# Buffers.net
KiCad netlist of a schematic drawn in Altium Designer
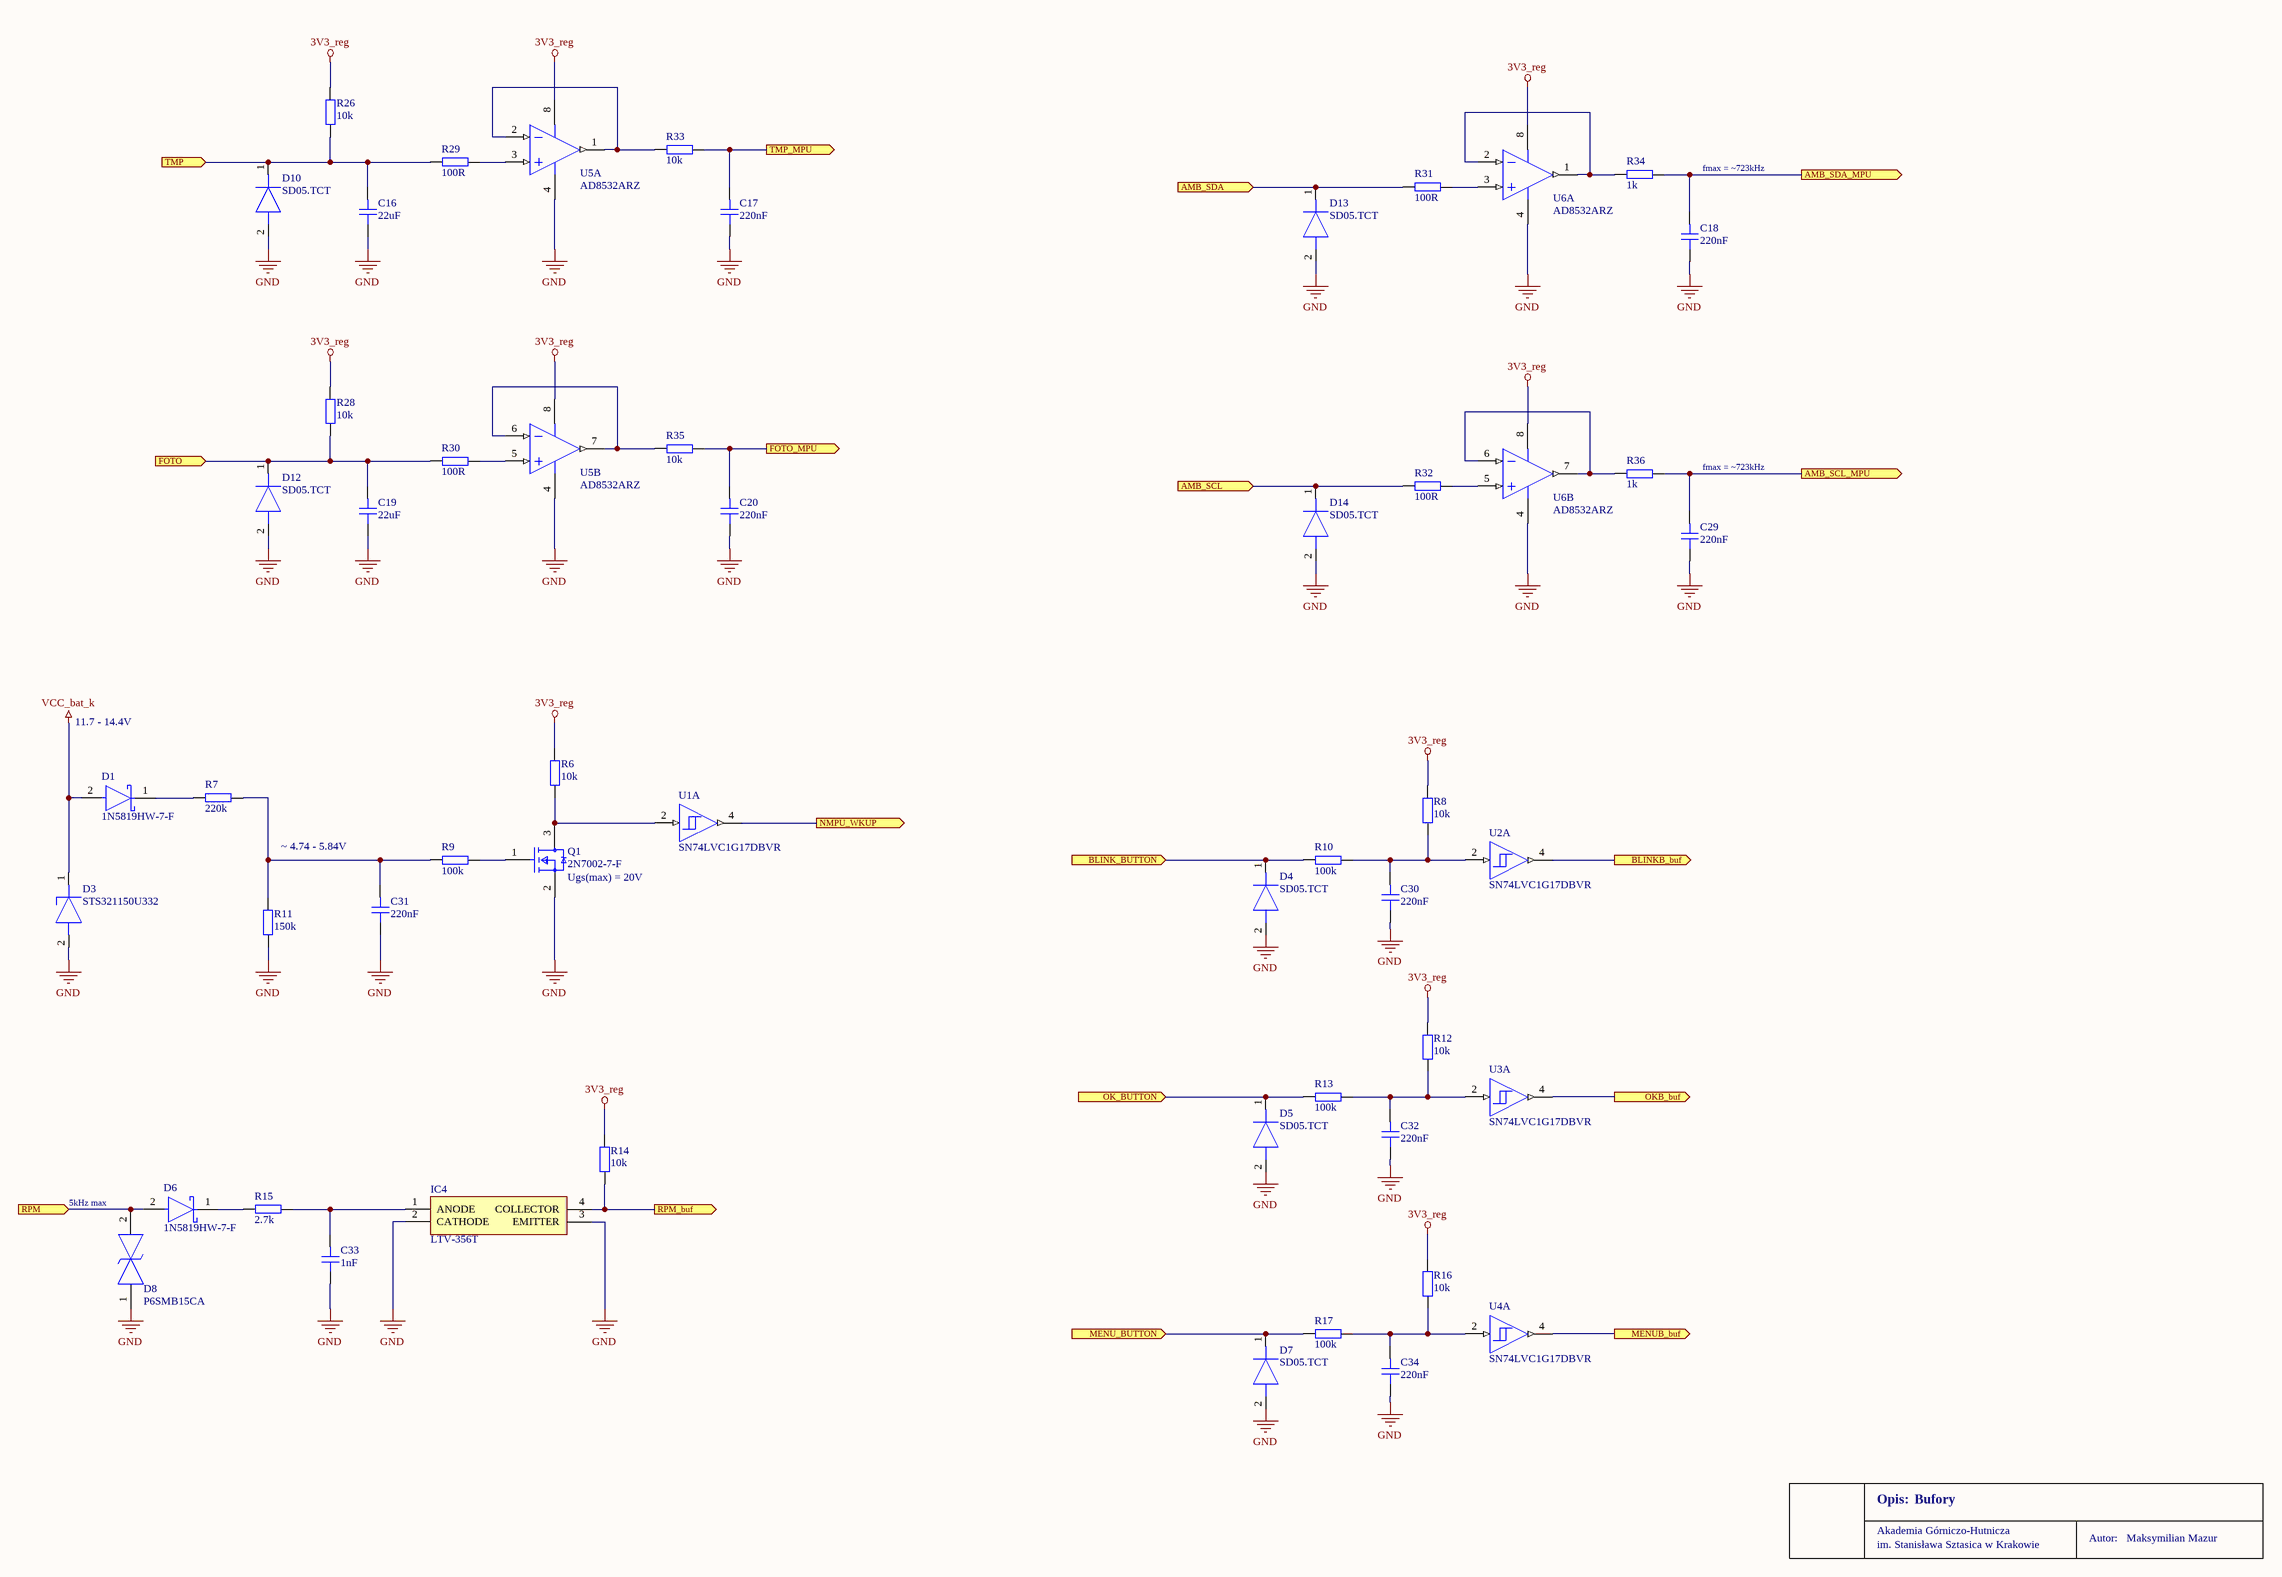
[diagram p0: Buffers.SchDoc]

(export (version "E")
  (design (tool "Eeschema 10.0.6"))
  (components
    (comp (ref "C16")
      (value "22uF")
      (footprint "CAP_0603")
      (description "Capacitor SMD 0603\r\nX7R\r\nLOW ESR")
      (libsource (lib "Schematic-Lib-PhilsLab") (part "CAP_0603"))
    )
    (comp (ref "C17")
      (value "220nF")
      (footprint "CAP_0603")
      (description "Capacitor SMD 0603\r\nX7R\r\nLOW ESR")
      (libsource (lib "Schematic-Lib-PhilsLab") (part "CAP_0603"))
    )
    (comp (ref "C18")
      (value "220nF")
      (footprint "CAP_0603")
      (description "Capacitor SMD 0603\r\nX7R\r\nLOW ESR")
      (libsource (lib "Schematic-Lib-PhilsLab") (part "CAP_0603"))
    )
    (comp (ref "C19")
      (value "22uF")
      (footprint "CAP_0603")
      (description "Capacitor SMD 0603\r\nX7R\r\nLOW ESR")
      (libsource (lib "Schematic-Lib-PhilsLab") (part "CAP_0603"))
    )
    (comp (ref "C20")
      (value "220nF")
      (footprint "CAP_0603")
      (description "Capacitor SMD 0603\r\nX7R\r\nLOW ESR")
      (libsource (lib "Schematic-Lib-PhilsLab") (part "CAP_0603"))
    )
    (comp (ref "C29")
      (value "220nF")
      (footprint "CAP_0603")
      (description "Capacitor SMD 0603\r\nX7R\r\nLOW ESR")
      (libsource (lib "Schematic-Lib-PhilsLab") (part "CAP_0603"))
    )
    (comp (ref "C30")
      (value "220nF")
      (footprint "CAP_0603")
      (description "Capacitor SMD 0603\r\nX7R\r\nLOW ESR")
      (libsource (lib "Schematic-Lib-PhilsLab") (part "CAP_0603"))
    )
    (comp (ref "C31")
      (value "220nF")
      (footprint "CAP_0603")
      (description "Capacitor SMD 0603\r\nX7R\r\nLOW ESR")
      (libsource (lib "Schematic-Lib-PhilsLab") (part "CAP_0603"))
    )
    (comp (ref "C32")
      (value "220nF")
      (footprint "CAP_0603")
      (description "Capacitor SMD 0603\r\nX7R\r\nLOW ESR")
      (libsource (lib "Schematic-Lib-PhilsLab") (part "CAP_0603"))
    )
    (comp (ref "C33")
      (value "1nF")
      (footprint "CAP_0603")
      (description "Capacitor SMD 0603\r\nX7R\r\nLOW ESR")
      (libsource (lib "Schematic-Lib-PhilsLab") (part "CAP_0603"))
    )
    (comp (ref "C34")
      (value "220nF")
      (footprint "CAP_0603")
      (description "Capacitor SMD 0603\r\nX7R\r\nLOW ESR")
      (libsource (lib "Schematic-Lib-PhilsLab") (part "CAP_0603"))
    )
    (comp (ref "D1")
      (value "1N5819HW-7-F")
      (footprint "FP-SOD123-IPC_A")
      (description "DIODE SCHOTTKY 40V 1A SOD123")
      (libsource (lib "Altium Content Vault") (part "1d6ec82d83fb6aee721767c19dac4b9"))
    )
    (comp (ref "D3")
      (value "STS321150U332")
      (footprint "SamacSys:SOD2613X100N")
      (description "Diode ESD (Uni-directional)\r\n\r\nSOD-323 \r\n16V 330pF")
      (fields (field (name "MANUFACTURER_PART_NUMBER") "STS321150U751"))
      (libsource (lib "*") (part "STS321150U751"))
    )
    (comp (ref "D4")
      (value "SD05.TCT")
      (footprint "SamacSys:SOD2513X110N")
      (description "Diode")
      (fields (field (name "MOUSER PART NUMBER") "947-SD05.TCT"))
      (libsource (lib "*") (part "SD05.TCT"))
    )
    (comp (ref "D5")
      (value "SD05.TCT")
      (footprint "SamacSys:SOD2513X110N")
      (description "Diode")
      (fields (field (name "MOUSER PART NUMBER") "947-SD05.TCT"))
      (libsource (lib "*") (part "SD05.TCT"))
    )
    (comp (ref "D6")
      (value "1N5819HW-7-F")
      (footprint "FP-SOD123-IPC_A")
      (description "DIODE SCHOTTKY 40V 1A SOD123")
      (libsource (lib "Altium Content Vault") (part "1d6ec82d83fb6aee721767c19dac4b9"))
    )
    (comp (ref "D7")
      (value "SD05.TCT")
      (footprint "SamacSys:SOD2513X110N")
      (description "Diode")
      (fields (field (name "MOUSER PART NUMBER") "947-SD05.TCT"))
      (libsource (lib "*") (part "SD05.TCT"))
    )
    (comp (ref "D8")
      (value "P6SMB15CA")
      (footprint "SamacSys:DIONM5436X261N")
      (description "TVS Diode (Bi-directional)")
      (fields (field (name "MOUSER PART NUMBER") "576-P6SMB15CA"))
      (libsource (lib "*") (part "P6SMB15CA"))
    )
    (comp (ref "D10")
      (value "SD05.TCT")
      (footprint "SamacSys:SOD2513X110N")
      (description "Diode")
      (fields (field (name "MOUSER PART NUMBER") "947-SD05.TCT"))
      (libsource (lib "*") (part "SD05.TCT"))
    )
    (comp (ref "D12")
      (value "SD05.TCT")
      (footprint "SamacSys:SOD2513X110N")
      (description "Diode")
      (fields (field (name "MOUSER PART NUMBER") "947-SD05.TCT"))
      (libsource (lib "*") (part "SD05.TCT"))
    )
    (comp (ref "D13")
      (value "SD05.TCT")
      (footprint "SamacSys:SOD2513X110N")
      (description "Diode")
      (fields (field (name "MOUSER PART NUMBER") "947-SD05.TCT"))
      (libsource (lib "*") (part "SD05.TCT"))
    )
    (comp (ref "D14")
      (value "SD05.TCT")
      (footprint "SamacSys:SOD2513X110N")
      (description "Diode")
      (fields (field (name "MOUSER PART NUMBER") "947-SD05.TCT"))
      (libsource (lib "*") (part "SD05.TCT"))
    )
    (comp (ref "IC4")
      (value "LTV-356T")
      (footprint "SamacSys:SOP254P675X220-4N")
      (description "Integrated Circuit")
      (fields (field (name "MOUSER PART NUMBER") "859-LTV-356T"))
      (libsource (lib "*") (part "LTV-356T"))
    )
    (comp (ref "Q1")
      (value "2N7002-7-F")
      (footprint "FP-SOT23-MFG")
      (description "MOSFET N-CH 60V 115MA SOT23-3")
      (fields (field (name "VOLTAGE") "60V"))
      (libsource (lib "Altium Content Vault") (part "3b9c635fedb024a5347a57b145af9cc"))
    )
    (comp (ref "R6")
      (value "10k")
      (footprint "RES_0603")
      (description "Resistor SMD 0603")
      (libsource (lib "Schematic-Lib-PhilsLab") (part "RES_0603"))
    )
    (comp (ref "R7")
      (value "220k")
      (footprint "RES_0603")
      (description "Resistor SMD 0603")
      (libsource (lib "Schematic-Lib-PhilsLab") (part "RES_0603"))
    )
    (comp (ref "R8")
      (value "10k")
      (footprint "RES_0603")
      (description "Resistor SMD 0603")
      (libsource (lib "Schematic-Lib-PhilsLab") (part "RES_0603"))
    )
    (comp (ref "R9")
      (value "100k")
      (footprint "RES_0603")
      (description "Resistor SMD 0603")
      (libsource (lib "Schematic-Lib-PhilsLab") (part "RES_0603"))
    )
    (comp (ref "R10")
      (value "100k")
      (footprint "RES_0603")
      (description "Resistor SMD 0603")
      (libsource (lib "Schematic-Lib-PhilsLab") (part "RES_0603"))
    )
    (comp (ref "R11")
      (value "150k")
      (footprint "RES_0603")
      (description "Resistor SMD 0603")
      (libsource (lib "Schematic-Lib-PhilsLab") (part "RES_0603"))
    )
    (comp (ref "R12")
      (value "10k")
      (footprint "RES_0603")
      (description "Resistor SMD 0603")
      (libsource (lib "Schematic-Lib-PhilsLab") (part "RES_0603"))
    )
    (comp (ref "R13")
      (value "100k")
      (footprint "RES_0603")
      (description "Resistor SMD 0603")
      (libsource (lib "Schematic-Lib-PhilsLab") (part "RES_0603"))
    )
    (comp (ref "R14")
      (value "10k")
      (footprint "RES_0603")
      (description "Resistor SMD 0603")
      (libsource (lib "Schematic-Lib-PhilsLab") (part "RES_0603"))
    )
    (comp (ref "R15")
      (value "2.7k")
      (footprint "RES_0603")
      (description "Resistor SMD 0603")
      (libsource (lib "Schematic-Lib-PhilsLab") (part "RES_0603"))
    )
    (comp (ref "R16")
      (value "10k")
      (footprint "RES_0603")
      (description "Resistor SMD 0603")
      (libsource (lib "Schematic-Lib-PhilsLab") (part "RES_0603"))
    )
    (comp (ref "R17")
      (value "100k")
      (footprint "RES_0603")
      (description "Resistor SMD 0603")
      (libsource (lib "Schematic-Lib-PhilsLab") (part "RES_0603"))
    )
    (comp (ref "R26")
      (value "10k")
      (footprint "RES_0603")
      (description "Resistor SMD 0603")
      (libsource (lib "Schematic-Lib-PhilsLab") (part "RES_0603"))
    )
    (comp (ref "R28")
      (value "10k")
      (footprint "RES_0603")
      (description "Resistor SMD 0603")
      (libsource (lib "Schematic-Lib-PhilsLab") (part "RES_0603"))
    )
    (comp (ref "R29")
      (value "100R")
      (footprint "RES_0603")
      (description "Resistor SMD 0603")
      (libsource (lib "Schematic-Lib-PhilsLab") (part "RES_0603"))
    )
    (comp (ref "R30")
      (value "100R")
      (footprint "RES_0603")
      (description "Resistor SMD 0603")
      (libsource (lib "Schematic-Lib-PhilsLab") (part "RES_0603"))
    )
    (comp (ref "R31")
      (value "100R")
      (footprint "RES_0603")
      (description "Resistor SMD 0603")
      (libsource (lib "Schematic-Lib-PhilsLab") (part "RES_0603"))
    )
    (comp (ref "R32")
      (value "100R")
      (footprint "RES_0603")
      (description "Resistor SMD 0603")
      (libsource (lib "Schematic-Lib-PhilsLab") (part "RES_0603"))
    )
    (comp (ref "R33")
      (value "10k")
      (footprint "RES_0603")
      (description "Resistor SMD 0603")
      (libsource (lib "Schematic-Lib-PhilsLab") (part "RES_0603"))
    )
    (comp (ref "R34")
      (value "1k")
      (footprint "RES_0603")
      (description "Resistor SMD 0603")
      (libsource (lib "Schematic-Lib-PhilsLab") (part "RES_0603"))
    )
    (comp (ref "R35")
      (value "10k")
      (footprint "RES_0603")
      (description "Resistor SMD 0603")
      (libsource (lib "Schematic-Lib-PhilsLab") (part "RES_0603"))
    )
    (comp (ref "R36")
      (value "1k")
      (footprint "RES_0603")
      (description "Resistor SMD 0603")
      (libsource (lib "Schematic-Lib-PhilsLab") (part "RES_0603"))
    )
    (comp (ref "U1")
      (value "SN74LVC1G17DBVR")
      (footprint "DBV0005A_L")
      (description "Single Schmitt-Trigger Buffer, DBV0005A, LARGE T&R")
      (fields
        (field (name "MANUFACTURER") "Texas Instruments")
        (field (name "GENERIC PART NUMBER") "SN74LVC1G17")
      )
      (libsource (lib "Altium Content Vault") (part "TI-SN74XXX1XXX-XX-5-SCHMITT"))
    )
    (comp (ref "U2")
      (value "SN74LVC1G17DBVR")
      (footprint "DBV0005A_L")
      (description "Single Schmitt-Trigger Buffer, DBV0005A, LARGE T&R")
      (fields
        (field (name "MANUFACTURER") "Texas Instruments")
        (field (name "GENERIC PART NUMBER") "SN74LVC1G17")
      )
      (libsource (lib "Altium Content Vault") (part "TI-SN74XXX1XXX-XX-5-SCHMITT"))
    )
    (comp (ref "U3")
      (value "SN74LVC1G17DBVR")
      (footprint "DBV0005A_L")
      (description "Single Schmitt-Trigger Buffer, DBV0005A, LARGE T&R")
      (fields
        (field (name "MANUFACTURER") "Texas Instruments")
        (field (name "GENERIC PART NUMBER") "SN74LVC1G17")
      )
      (libsource (lib "Altium Content Vault") (part "TI-SN74XXX1XXX-XX-5-SCHMITT"))
    )
    (comp (ref "U4")
      (value "SN74LVC1G17DBVR")
      (footprint "DBV0005A_L")
      (description "Single Schmitt-Trigger Buffer, DBV0005A, LARGE T&R")
      (fields
        (field (name "MANUFACTURER") "Texas Instruments")
        (field (name "GENERIC PART NUMBER") "SN74LVC1G17")
      )
      (libsource (lib "Altium Content Vault") (part "TI-SN74XXX1XXX-XX-5-SCHMITT"))
    )
    (comp (ref "U5")
      (value "AD8532ARZ")
      (footprint "ADI-R-8_L")
      (fields (field (name "GENERIC PART NUMBER") "AD8532") (field (name "MANUFACTURER") "Analog Devices"))
      (libsource (lib "Altium Content Vault") (part "ADI-OP29X-R-8"))
    )
    (comp (ref "U6")
      (value "AD8532ARZ")
      (footprint "ADI-R-8_L")
      (fields (field (name "GENERIC PART NUMBER") "AD8532") (field (name "MANUFACTURER") "Analog Devices"))
      (libsource (lib "Altium Content Vault") (part "ADI-OP29X-R-8"))
    )
  )
  (nets
    (net (code "1") (name "/AMB_SCL") (class "Default")
      (node (ref "D14") (pin "1") (pinfunction "K_1") (pintype "passive"))
      (node (ref "R32") (pin "2") (pinfunction "2_2") (pintype "passive"))
    )
    (net (code "2") (name "/AMB_SCL_MPU") (class "Default")
      (node (ref "C29") (pin "1") (pinfunction "1_1") (pintype "passive"))
      (node (ref "R36") (pin "1") (pinfunction "1_1") (pintype "passive"))
    )
    (net (code "3") (name "/AMB_SDA") (class "Default")
      (node (ref "D13") (pin "1") (pinfunction "K_1") (pintype "passive"))
      (node (ref "R31") (pin "2") (pinfunction "2_2") (pintype "passive"))
    )
    (net (code "4") (name "/AMB_SDA_MPU") (class "Default")
      (node (ref "C18") (pin "1") (pinfunction "1_1") (pintype "passive"))
      (node (ref "R34") (pin "1") (pinfunction "1_1") (pintype "passive"))
    )
    (net (code "5") (name "/BLINKB_buf") (class "Default")
      (node (ref "U2") (pin "4") (pinfunction "Y_4") (pintype "output"))
    )
    (net (code "6") (name "/BLINK_BUTTON") (class "Default")
      (node (ref "D4") (pin "1") (pinfunction "K_1") (pintype "passive"))
      (node (ref "R10") (pin "2") (pinfunction "2_2") (pintype "passive"))
    )
    (net (code "7") (name "/FOTO") (class "Default")
      (node (ref "C19") (pin "1") (pinfunction "1_1") (pintype "passive"))
      (node (ref "D12") (pin "1") (pinfunction "K_1") (pintype "passive"))
      (node (ref "R28") (pin "1") (pinfunction "1_1") (pintype "passive"))
      (node (ref "R30") (pin "2") (pinfunction "2_2") (pintype "passive"))
    )
    (net (code "8") (name "/FOTO_MPU") (class "Default")
      (node (ref "C20") (pin "1") (pinfunction "1_1") (pintype "passive"))
      (node (ref "R35") (pin "1") (pinfunction "1_1") (pintype "passive"))
    )
    (net (code "9") (name "/MENUB_buf") (class "Default")
      (node (ref "U4") (pin "4") (pinfunction "Y_4") (pintype "output"))
    )
    (net (code "10") (name "/MENU_BUTTON") (class "Default")
      (node (ref "D7") (pin "1") (pinfunction "K_1") (pintype "passive"))
      (node (ref "R17") (pin "2") (pinfunction "2_2") (pintype "passive"))
    )
    (net (code "11") (name "/NMPU_WKUP") (class "Default")
      (node (ref "U1") (pin "4") (pinfunction "Y_4") (pintype "output"))
    )
    (net (code "12") (name "/OKB_buf") (class "Default")
      (node (ref "U3") (pin "4") (pinfunction "Y_4") (pintype "output"))
    )
    (net (code "13") (name "/OK_BUTTON") (class "Default")
      (node (ref "D5") (pin "1") (pinfunction "K_1") (pintype "passive"))
      (node (ref "R13") (pin "2") (pinfunction "2_2") (pintype "passive"))
    )
    (net (code "14") (name "/RPM") (class "Default")
      (node (ref "D6") (pin "2") (pinfunction "A_2") (pintype "passive"))
      (node (ref "D8") (pin "2") (pinfunction "2_2") (pintype "passive"))
    )
    (net (code "15") (name "/RPM_buf") (class "Default")
      (node (ref "IC4") (pin "4") (pinfunction "COLLECTOR_4") (pintype "passive"))
      (node (ref "R14") (pin "2") (pinfunction "2_2") (pintype "passive"))
    )
    (net (code "16") (name "/TMP") (class "Default")
      (node (ref "C16") (pin "1") (pinfunction "1_1") (pintype "passive"))
      (node (ref "D10") (pin "1") (pinfunction "K_1") (pintype "passive"))
      (node (ref "R26") (pin "1") (pinfunction "1_1") (pintype "passive"))
      (node (ref "R29") (pin "2") (pinfunction "2_2") (pintype "passive"))
    )
    (net (code "17") (name "/TMP_MPU") (class "Default")
      (node (ref "C17") (pin "1") (pinfunction "1_1") (pintype "passive"))
      (node (ref "R33") (pin "1") (pinfunction "1_1") (pintype "passive"))
    )
    (net (code "18") (name "3V3_reg") (class "Default")
      (node (ref "R12") (pin "1") (pinfunction "1_1") (pintype "passive"))
      (node (ref "R14") (pin "1") (pinfunction "1_1") (pintype "passive"))
      (node (ref "R16") (pin "1") (pinfunction "1_1") (pintype "passive"))
      (node (ref "R26") (pin "2") (pinfunction "2_2") (pintype "passive"))
      (node (ref "R28") (pin "2") (pinfunction "2_2") (pintype "passive"))
      (node (ref "R6") (pin "1") (pinfunction "1_1") (pintype "passive"))
      (node (ref "R8") (pin "1") (pinfunction "1_1") (pintype "passive"))
      (node (ref "U5") (pin "8") (pinfunction "+V_8") (pintype "power_in"))
      (node (ref "U6") (pin "8") (pinfunction "+V_8") (pintype "power_in"))
    )
    (net (code "19") (name "GND") (class "Default")
      (node (ref "C16") (pin "2") (pinfunction "2_2") (pintype "passive"))
      (node (ref "C17") (pin "2") (pinfunction "2_2") (pintype "passive"))
      (node (ref "C18") (pin "2") (pinfunction "2_2") (pintype "passive"))
      (node (ref "C19") (pin "2") (pinfunction "2_2") (pintype "passive"))
      (node (ref "C20") (pin "2") (pinfunction "2_2") (pintype "passive"))
      (node (ref "C29") (pin "2") (pinfunction "2_2") (pintype "passive"))
      (node (ref "C30") (pin "2") (pinfunction "2_2") (pintype "passive"))
      (node (ref "C31") (pin "2") (pinfunction "2_2") (pintype "passive"))
      (node (ref "C32") (pin "2") (pinfunction "2_2") (pintype "passive"))
      (node (ref "C33") (pin "2") (pinfunction "2_2") (pintype "passive"))
      (node (ref "C34") (pin "2") (pinfunction "2_2") (pintype "passive"))
      (node (ref "D10") (pin "2") (pinfunction "A_2") (pintype "passive"))
      (node (ref "D12") (pin "2") (pinfunction "A_2") (pintype "passive"))
      (node (ref "D13") (pin "2") (pinfunction "A_2") (pintype "passive"))
      (node (ref "D14") (pin "2") (pinfunction "A_2") (pintype "passive"))
      (node (ref "D3") (pin "2") (pinfunction "A_2") (pintype "passive"))
      (node (ref "D4") (pin "2") (pinfunction "A_2") (pintype "passive"))
      (node (ref "D5") (pin "2") (pinfunction "A_2") (pintype "passive"))
      (node (ref "D7") (pin "2") (pinfunction "A_2") (pintype "passive"))
      (node (ref "D8") (pin "1") (pinfunction "1_1") (pintype "passive"))
      (node (ref "IC4") (pin "2") (pinfunction "CATHODE_2") (pintype "passive"))
      (node (ref "IC4") (pin "3") (pinfunction "EMITTER_3") (pintype "passive"))
      (node (ref "Q1") (pin "2") (pinfunction "S_2") (pintype "passive"))
      (node (ref "R11") (pin "2") (pinfunction "2_2") (pintype "passive"))
      (node (ref "U5") (pin "4") (pinfunction "-V_4") (pintype "power_in"))
      (node (ref "U6") (pin "4") (pinfunction "-V_4") (pintype "power_in"))
    )
    (net (code "20") (name "Net-(C31-Pad1)") (class "Default")
      (node (ref "C31") (pin "1") (pinfunction "1_1") (pintype "passive"))
      (node (ref "R11") (pin "1") (pinfunction "1_1") (pintype "passive"))
      (node (ref "R7") (pin "1") (pinfunction "1_1") (pintype "passive"))
      (node (ref "R9") (pin "2") (pinfunction "2_2") (pintype "passive"))
    )
    (net (code "21") (name "Net-(D1-C)") (class "Default")
      (node (ref "D1") (pin "1") (pinfunction "C_1") (pintype "passive"))
      (node (ref "R7") (pin "2") (pinfunction "2_2") (pintype "passive"))
    )
    (net (code "22") (name "Net-(D6-C)") (class "Default")
      (node (ref "D6") (pin "1") (pinfunction "C_1") (pintype "passive"))
      (node (ref "R15") (pin "2") (pinfunction "2_2") (pintype "passive"))
    )
    (net (code "23") (name "Net-(IC4-ANODE)") (class "Default")
      (node (ref "C33") (pin "1") (pinfunction "1_1") (pintype "passive"))
      (node (ref "IC4") (pin "1") (pinfunction "ANODE_1") (pintype "passive"))
      (node (ref "R15") (pin "1") (pinfunction "1_1") (pintype "passive"))
    )
    (net (code "24") (name "Net-(Q1-D)") (class "Default")
      (node (ref "Q1") (pin "3") (pinfunction "D_3") (pintype "passive"))
      (node (ref "R6") (pin "2") (pinfunction "2_2") (pintype "passive"))
      (node (ref "U1") (pin "2") (pinfunction "A_2") (pintype "input"))
    )
    (net (code "25") (name "Net-(Q1-G)") (class "Default")
      (node (ref "Q1") (pin "1") (pinfunction "G_1") (pintype "passive"))
      (node (ref "R9") (pin "1") (pinfunction "1_1") (pintype "passive"))
    )
    (net (code "26") (name "Net-(U2A-A)") (class "Default")
      (node (ref "C30") (pin "1") (pinfunction "1_1") (pintype "passive"))
      (node (ref "R10") (pin "1") (pinfunction "1_1") (pintype "passive"))
      (node (ref "R8") (pin "2") (pinfunction "2_2") (pintype "passive"))
      (node (ref "U2") (pin "2") (pinfunction "A_2") (pintype "input"))
    )
    (net (code "27") (name "Net-(U3A-A)") (class "Default")
      (node (ref "C32") (pin "1") (pinfunction "1_1") (pintype "passive"))
      (node (ref "R12") (pin "2") (pinfunction "2_2") (pintype "passive"))
      (node (ref "R13") (pin "1") (pinfunction "1_1") (pintype "passive"))
      (node (ref "U3") (pin "2") (pinfunction "A_2") (pintype "input"))
    )
    (net (code "28") (name "Net-(U4A-A)") (class "Default")
      (node (ref "C34") (pin "1") (pinfunction "1_1") (pintype "passive"))
      (node (ref "R16") (pin "2") (pinfunction "2_2") (pintype "passive"))
      (node (ref "R17") (pin "1") (pinfunction "1_1") (pintype "passive"))
      (node (ref "U4") (pin "2") (pinfunction "A_2") (pintype "input"))
    )
    (net (code "29") (name "Net-(U5A-+IN_A)") (class "Default")
      (node (ref "R29") (pin "1") (pinfunction "1_1") (pintype "passive"))
      (node (ref "U5") (pin "3") (pinfunction "+IN_A_3") (pintype "input"))
    )
    (net (code "30") (name "Net-(U5A--IN_A)") (class "Default")
      (node (ref "R33") (pin "2") (pinfunction "2_2") (pintype "passive"))
      (node (ref "U5") (pin "1") (pinfunction "OUT_A_1") (pintype "output"))
      (node (ref "U5") (pin "2") (pinfunction "-IN_A_2") (pintype "input"))
    )
    (net (code "31") (name "Net-(U5B-+IN_B)") (class "Default")
      (node (ref "R30") (pin "1") (pinfunction "1_1") (pintype "passive"))
      (node (ref "U5") (pin "5") (pinfunction "+IN_B_5") (pintype "input"))
    )
    (net (code "32") (name "Net-(U5B--IN_B)") (class "Default")
      (node (ref "R35") (pin "2") (pinfunction "2_2") (pintype "passive"))
      (node (ref "U5") (pin "6") (pinfunction "-IN_B_6") (pintype "input"))
      (node (ref "U5") (pin "7") (pinfunction "OUT_B_7") (pintype "output"))
    )
    (net (code "33") (name "Net-(U6A-+IN_A)") (class "Default")
      (node (ref "R31") (pin "1") (pinfunction "1_1") (pintype "passive"))
      (node (ref "U6") (pin "3") (pinfunction "+IN_A_3") (pintype "input"))
    )
    (net (code "34") (name "Net-(U6A--IN_A)") (class "Default")
      (node (ref "R34") (pin "2") (pinfunction "2_2") (pintype "passive"))
      (node (ref "U6") (pin "1") (pinfunction "OUT_A_1") (pintype "output"))
      (node (ref "U6") (pin "2") (pinfunction "-IN_A_2") (pintype "input"))
    )
    (net (code "35") (name "Net-(U6B-+IN_B)") (class "Default")
      (node (ref "R32") (pin "1") (pinfunction "1_1") (pintype "passive"))
      (node (ref "U6") (pin "5") (pinfunction "+IN_B_5") (pintype "input"))
    )
    (net (code "36") (name "Net-(U6B--IN_B)") (class "Default")
      (node (ref "R36") (pin "2") (pinfunction "2_2") (pintype "passive"))
      (node (ref "U6") (pin "6") (pinfunction "-IN_B_6") (pintype "input"))
      (node (ref "U6") (pin "7") (pinfunction "OUT_B_7") (pintype "output"))
    )
    (net (code "37") (name "VCC_bat_k") (class "Default")
      (node (ref "D1") (pin "2") (pinfunction "A_2") (pintype "passive"))
      (node (ref "D3") (pin "1") (pinfunction "K_1") (pintype "passive"))
    )
  )
)
